# MCU4.net
KiCad netlist of a schematic drawn in Altium Designer
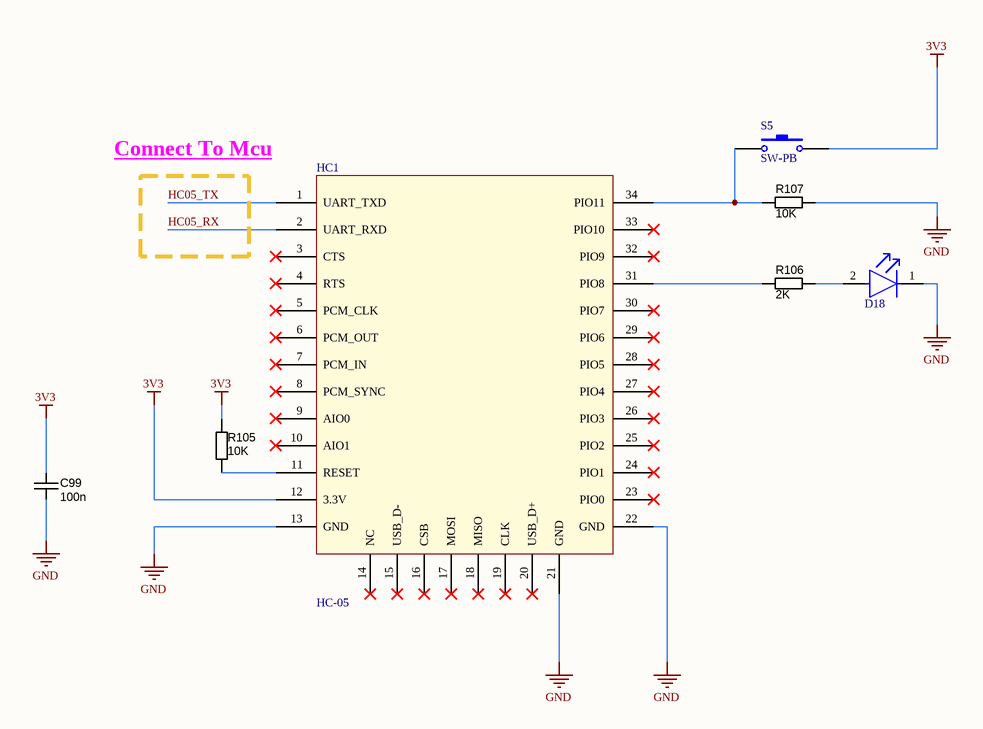
[diagram p0: MCU4.SchDoc]

(export (version "E")
  (design (tool "Eeschema 10.0.6"))
  (components
    (comp (ref "C99")
      (value "100n")
      (footprint "CAPC1608X90N")
      (description "Capacitor SMD Cer 100nF 10% 50V X7R 0603")
      (fields (field (name "TOLERANCE") "±10%") (field (name "Comment") "approved sub OK"))
      (libsource (lib "PBL - Capacitors") (part "CAPC_100n_0603_X7R_50V_10%"))
    )
    (comp (ref "D18")
      (value "LTST-C191TBKT")
      (footprint "FP-LTST-C191TBKT-MFG")
      (description "LED BLUE CLEAR CHIP SMD")
      (libsource (lib "Altium Content Vault") (part "8706943c75ba83719d021d2fdc84c58"))
    )
    (comp (ref "HC1") (value "HC-05") (footprint "HC-05") (libsource (lib "Module") (part "HC-05")))
    (comp (ref "R105")
      (value "10K")
      (footprint "RESC1608X55N")
      (description "Resistor SMD chip 10k Ohm 0.1W 5% 0603")
      (fields (field (name "TOLERANCE") "±5%") (field (name "Comment") "Thick Film"))
      (libsource (lib "") (part "RES_4K7_0603_5%_1"))
    )
    (comp (ref "R106")
      (value "2K")
      (footprint "RESC1608X55N")
      (description "Resistor SMD chip 2k Ohm 0.1W 5% 0603")
      (fields (field (name "TOLERANCE") "±5%") (field (name "Comment") "Thick Film"))
      (libsource (lib "PBL - Resistors") (part "RES_4K7_0603_5%"))
    )
    (comp (ref "R107")
      (value "10K")
      (footprint "RESC1608X55N")
      (description "Resistor SMD chip 10k Ohm 0.1W 5% 0603")
      (fields (field (name "TOLERANCE") "±5%") (field (name "Comment") "Thick Film"))
      (libsource (lib "PBL - Resistors") (part "RES_4K7_0603_5%"))
    )
    (comp (ref "S5")
      (value "SW-PB")
      (footprint "SWPBS_SPST_6X3X5")
      (description "Switch")
      (fields (field (name "PUBLISHER") "Altium Limited"))
      (libsource (lib "Miscellaneous Devices") (part "SW-PB"))
    )
  )
  (nets
    (net (code "1") (name "/HC05_RX") (class "Default")
      (node (ref "HC1") (pin "2") (pinfunction "UART_RXD_2") (pintype "passive"))
    )
    (net (code "2") (name "/HC05_TX") (class "Default")
      (node (ref "HC1") (pin "1") (pinfunction "UART_TXD_1") (pintype "passive"))
    )
    (net (code "3") (name "3V3") (class "Default")
      (node (ref "C99") (pin "1") (pintype "passive"))
      (node (ref "HC1") (pin "12") (pinfunction "3.3V_12") (pintype "passive"))
      (node (ref "R105") (pin "2") (pinfunction "2_2") (pintype "passive"))
      (node (ref "S5") (pin "1") (pinfunction "1_1") (pintype "passive"))
    )
    (net (code "4") (name "GND") (class "Default")
      (node (ref "C99") (pin "2") (pintype "passive"))
      (node (ref "D18") (pin "1") (pinfunction "C_1") (pintype "passive"))
      (node (ref "HC1") (pin "13") (pinfunction "GND_13") (pintype "passive"))
      (node (ref "HC1") (pin "21") (pinfunction "GND_21") (pintype "passive"))
      (node (ref "HC1") (pin "22") (pinfunction "GND_22") (pintype "passive"))
      (node (ref "R107") (pin "2") (pinfunction "2_2") (pintype "passive"))
    )
    (net (code "5") (name "Net-(D18-A)") (class "Default")
      (node (ref "D18") (pin "2") (pinfunction "A_2") (pintype "passive"))
      (node (ref "R106") (pin "2") (pinfunction "2_2") (pintype "passive"))
    )
    (net (code "6") (name "Net-(HC1-PIO8)") (class "Default")
      (node (ref "HC1") (pin "31") (pinfunction "PIO8_31") (pintype "passive"))
      (node (ref "R106") (pin "1") (pinfunction "1_1") (pintype "passive"))
    )
    (net (code "7") (name "Net-(HC1-PIO11)") (class "Default")
      (node (ref "HC1") (pin "34") (pinfunction "PIO11_34") (pintype "passive"))
      (node (ref "R107") (pin "1") (pinfunction "1_1") (pintype "passive"))
      (node (ref "S5") (pin "2") (pinfunction "2_2") (pintype "passive"))
    )
    (net (code "8") (name "Net-(HC1-RESET)") (class "Default")
      (node (ref "HC1") (pin "11") (pinfunction "RESET_11") (pintype "passive"))
      (node (ref "R105") (pin "1") (pinfunction "1_1") (pintype "passive"))
    )
    (net (code "9") (name "unconnected-(HC1-AIO0-Pad9)") (class "Default")
      (node (ref "HC1") (pin "9") (pinfunction "AIO0_9") (pintype "passive+no_connect"))
    )
    (net (code "10") (name "unconnected-(HC1-AIO1-Pad10)") (class "Default")
      (node (ref "HC1") (pin "10") (pinfunction "AIO1_10") (pintype "passive+no_connect"))
    )
    (net (code "11") (name "unconnected-(HC1-CLK-Pad19)") (class "Default")
      (node (ref "HC1") (pin "19") (pinfunction "CLK_19") (pintype "passive+no_connect"))
    )
    (net (code "12") (name "unconnected-(HC1-CSB-Pad16)") (class "Default")
      (node (ref "HC1") (pin "16") (pinfunction "CSB_16") (pintype "passive+no_connect"))
    )
    (net (code "13") (name "unconnected-(HC1-CTS-Pad3)") (class "Default")
      (node (ref "HC1") (pin "3") (pinfunction "CTS_3") (pintype "passive+no_connect"))
    )
    (net (code "14") (name "unconnected-(HC1-MISO-Pad18)") (class "Default")
      (node (ref "HC1") (pin "18") (pinfunction "MISO_18") (pintype "passive+no_connect"))
    )
    (net (code "15") (name "unconnected-(HC1-MOSI-Pad17)") (class "Default")
      (node (ref "HC1") (pin "17") (pinfunction "MOSI_17") (pintype "passive+no_connect"))
    )
    (net (code "16") (name "unconnected-(HC1-NC-Pad14)") (class "Default")
      (node (ref "HC1") (pin "14") (pinfunction "NC_14") (pintype "passive+no_connect"))
    )
    (net (code "17") (name "unconnected-(HC1-PCM_CLK-Pad5)") (class "Default")
      (node (ref "HC1") (pin "5") (pinfunction "PCM_CLK_5") (pintype "passive+no_connect"))
    )
    (net (code "18") (name "unconnected-(HC1-PCM_IN-Pad7)") (class "Default")
      (node (ref "HC1") (pin "7") (pinfunction "PCM_IN_7") (pintype "passive+no_connect"))
    )
    (net (code "19") (name "unconnected-(HC1-PCM_OUT-Pad6)") (class "Default")
      (node (ref "HC1") (pin "6") (pinfunction "PCM_OUT_6") (pintype "passive+no_connect"))
    )
    (net (code "20") (name "unconnected-(HC1-PCM_SYNC-Pad8)") (class "Default")
      (node (ref "HC1") (pin "8") (pinfunction "PCM_SYNC_8") (pintype "passive+no_connect"))
    )
    (net (code "21") (name "unconnected-(HC1-PIO0-Pad23)") (class "Default")
      (node (ref "HC1") (pin "23") (pinfunction "PIO0_23") (pintype "passive+no_connect"))
    )
    (net (code "22") (name "unconnected-(HC1-PIO1-Pad24)") (class "Default")
      (node (ref "HC1") (pin "24") (pinfunction "PIO1_24") (pintype "passive+no_connect"))
    )
    (net (code "23") (name "unconnected-(HC1-PIO2-Pad25)") (class "Default")
      (node (ref "HC1") (pin "25") (pinfunction "PIO2_25") (pintype "passive+no_connect"))
    )
    (net (code "24") (name "unconnected-(HC1-PIO3-Pad26)") (class "Default")
      (node (ref "HC1") (pin "26") (pinfunction "PIO3_26") (pintype "passive+no_connect"))
    )
    (net (code "25") (name "unconnected-(HC1-PIO4-Pad27)") (class "Default")
      (node (ref "HC1") (pin "27") (pinfunction "PIO4_27") (pintype "passive+no_connect"))
    )
    (net (code "26") (name "unconnected-(HC1-PIO5-Pad28)") (class "Default")
      (node (ref "HC1") (pin "28") (pinfunction "PIO5_28") (pintype "passive+no_connect"))
    )
    (net (code "27") (name "unconnected-(HC1-PIO6-Pad29)") (class "Default")
      (node (ref "HC1") (pin "29") (pinfunction "PIO6_29") (pintype "passive+no_connect"))
    )
    (net (code "28") (name "unconnected-(HC1-PIO7-Pad30)") (class "Default")
      (node (ref "HC1") (pin "30") (pinfunction "PIO7_30") (pintype "passive+no_connect"))
    )
    (net (code "29") (name "unconnected-(HC1-PIO9-Pad32)") (class "Default")
      (node (ref "HC1") (pin "32") (pinfunction "PIO9_32") (pintype "passive+no_connect"))
    )
    (net (code "30") (name "unconnected-(HC1-PIO10-Pad33)") (class "Default")
      (node (ref "HC1") (pin "33") (pinfunction "PIO10_33") (pintype "passive+no_connect"))
    )
    (net (code "31") (name "unconnected-(HC1-RTS-Pad4)") (class "Default")
      (node (ref "HC1") (pin "4") (pinfunction "RTS_4") (pintype "passive+no_connect"))
    )
    (net (code "32") (name "unconnected-(HC1-USB_D+-Pad20)") (class "Default")
      (node (ref "HC1") (pin "20") (pinfunction "USB_D+_20") (pintype "passive+no_connect"))
    )
    (net (code "33") (name "unconnected-(HC1-USB_D--Pad15)") (class "Default")
      (node (ref "HC1") (pin "15") (pinfunction "USB_D-_15") (pintype "passive+no_connect"))
    )
  )
)
